# SCH_1_Controller.net
KiCad netlist of a schematic drawn in Altium Designer
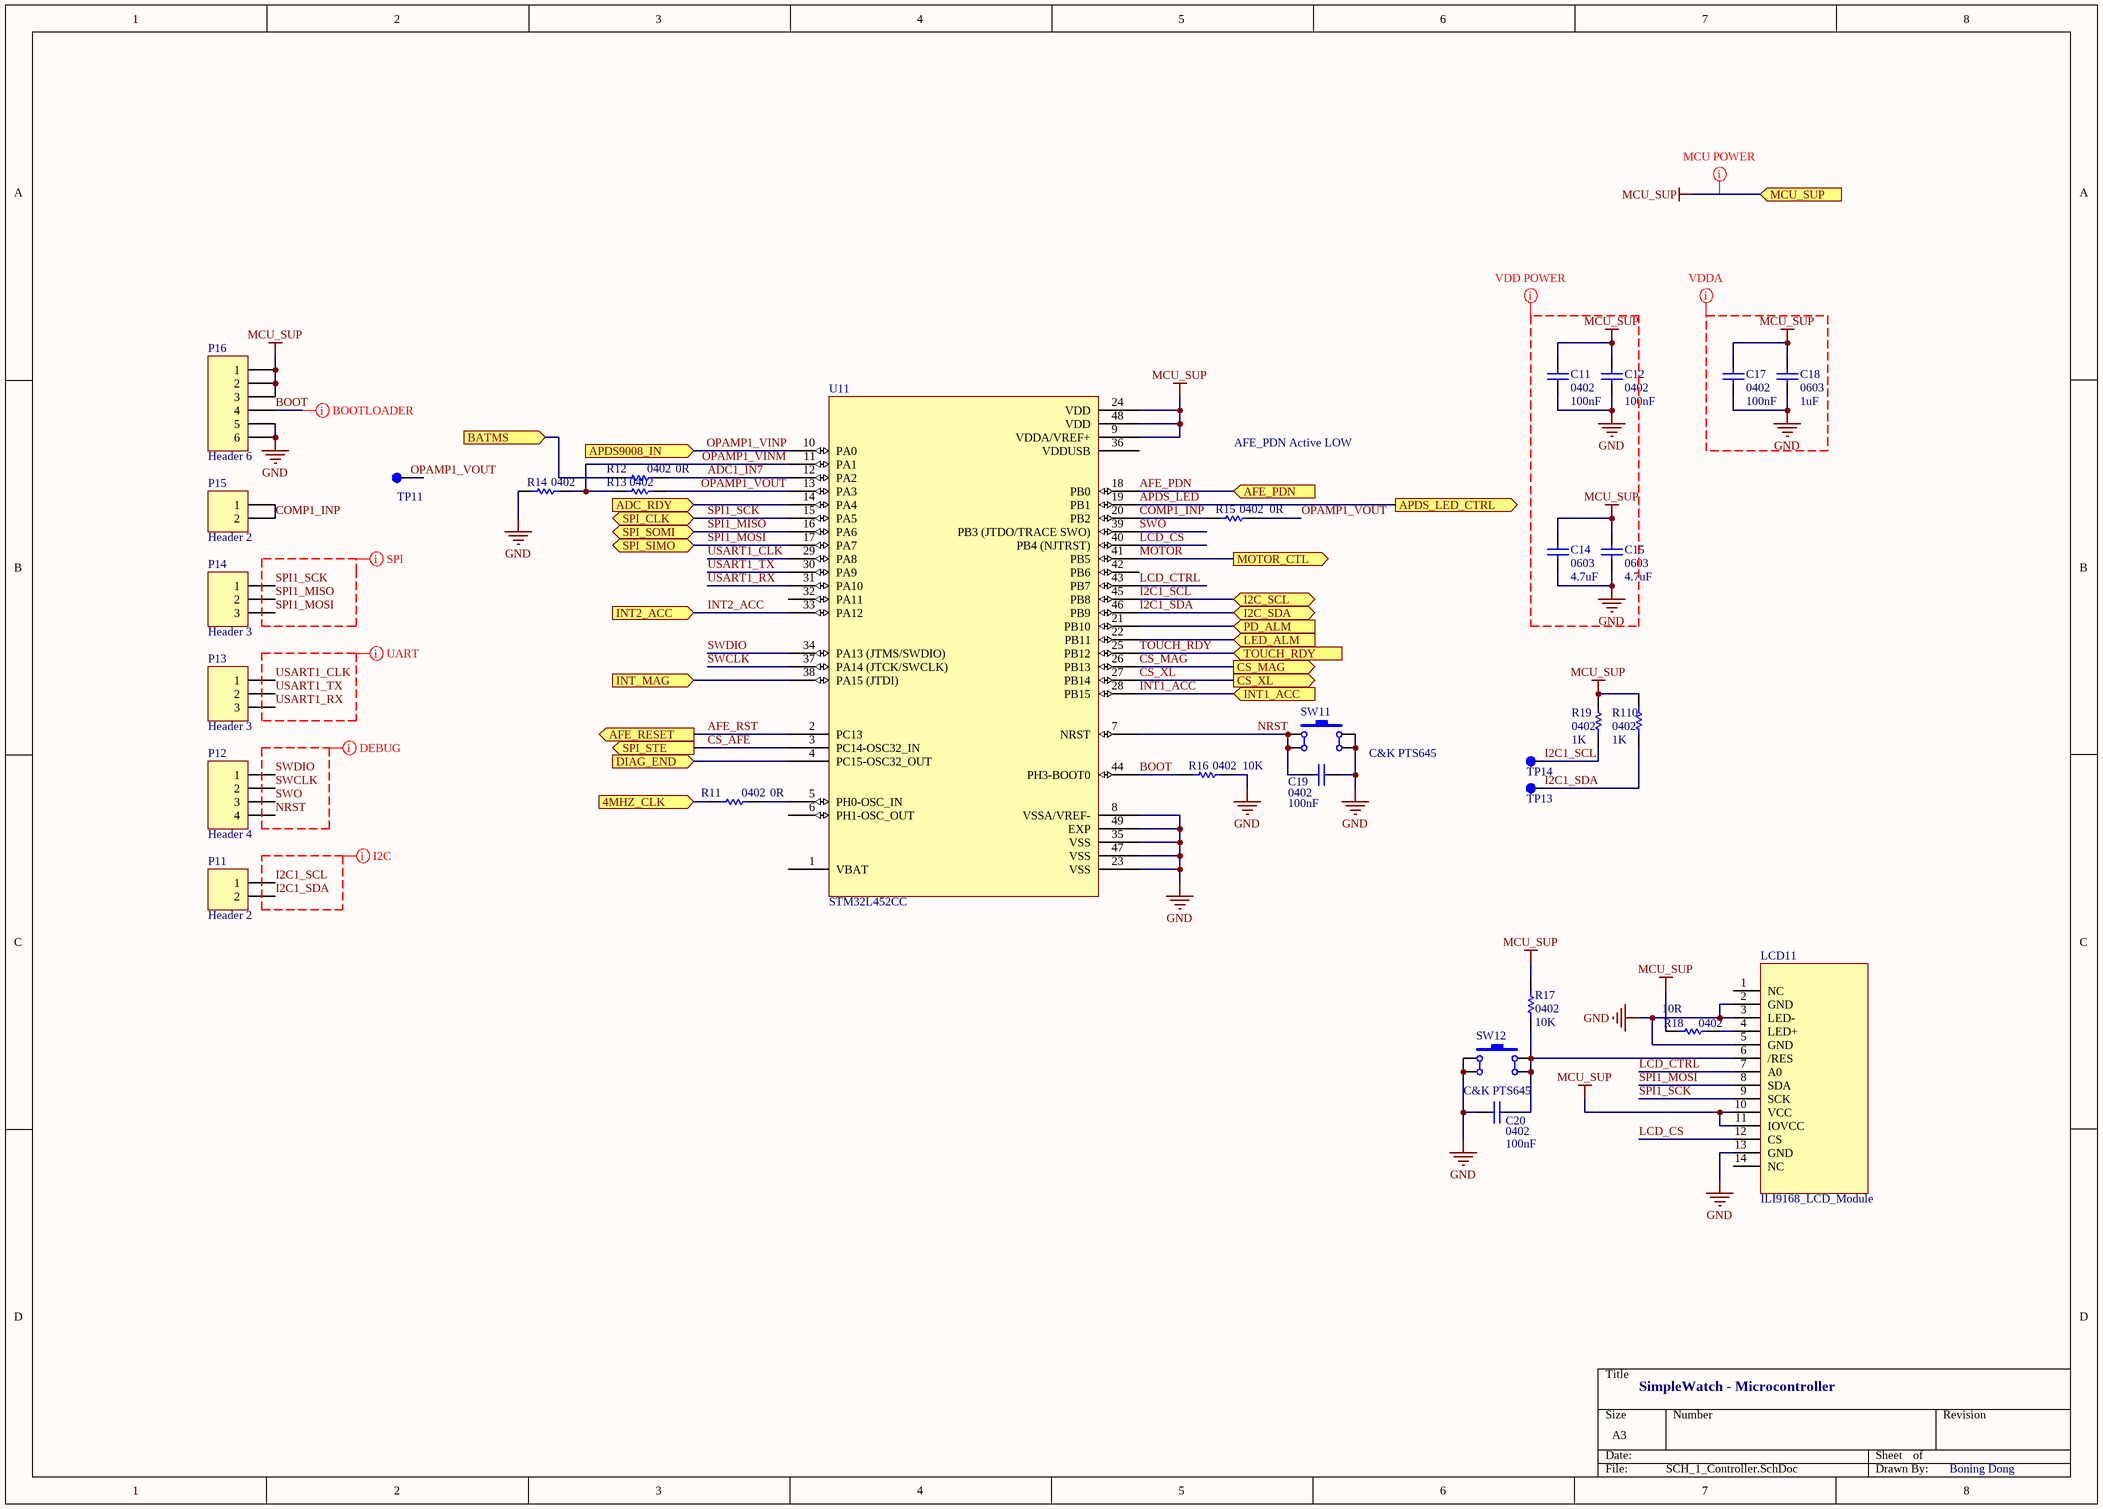
[diagram p0: SCH_1_Controller.SchDoc]

(export (version "E")
  (design (tool "Eeschema 10.0.6"))
  (components
    (comp (ref "C11")
      (value "0402")
      (footprint "CAPC1005X06N")
      (description "Capacitor")
      (fields (field (name "ALTIUM_VALUE") "100nF") (field (name "PUBLISHER") "Altium Limited"))
      (libsource (lib "Miscellaneous Devices") (part "Cap"))
    )
    (comp (ref "C12")
      (value "0402")
      (footprint "CAPC1005X06N")
      (description "Capacitor")
      (fields (field (name "ALTIUM_VALUE") "100nF") (field (name "PUBLISHER") "Altium Limited"))
      (libsource (lib "Miscellaneous Devices") (part "Cap"))
    )
    (comp (ref "C14")
      (value "0603")
      (footprint "CAPC1608X09N")
      (description "Capacitor")
      (fields (field (name "ALTIUM_VALUE") "4.7uF") (field (name "PUBLISHER") "Altium Limited"))
      (libsource (lib "Miscellaneous Devices") (part "Cap"))
    )
    (comp (ref "C15")
      (value "0603")
      (footprint "CAPC1608X09N")
      (description "Capacitor")
      (fields (field (name "ALTIUM_VALUE") "4.7uF") (field (name "PUBLISHER") "Altium Limited"))
      (libsource (lib "Miscellaneous Devices") (part "Cap"))
    )
    (comp (ref "C17")
      (value "0402")
      (footprint "CAPC1005X06N")
      (description "Capacitor")
      (fields (field (name "ALTIUM_VALUE") "100nF") (field (name "PUBLISHER") "Altium Limited"))
      (libsource (lib "Miscellaneous Devices") (part "Cap"))
    )
    (comp (ref "C18")
      (value "0603")
      (footprint "CAPC1608X09N")
      (description "Capacitor")
      (fields (field (name "ALTIUM_VALUE") "1uF") (field (name "PUBLISHER") "Altium Limited"))
      (libsource (lib "Miscellaneous Devices") (part "Cap"))
    )
    (comp (ref "C19")
      (value "0402")
      (footprint "CAPC1005X06N")
      (description "Capacitor")
      (fields (field (name "ALTIUM_VALUE") "100nF") (field (name "PUBLISHER") "Altium Limited"))
      (libsource (lib "Miscellaneous Devices") (part "Cap"))
    )
    (comp (ref "C20")
      (value "0402")
      (footprint "CAPC1005X06N")
      (description "Capacitor")
      (fields (field (name "ALTIUM_VALUE") "100nF") (field (name "PUBLISHER") "Altium Limited"))
      (libsource (lib "Miscellaneous Devices") (part "Cap"))
    )
    (comp (ref "LCD11")
      (value "ILI9168_LCD_Module")
      (footprint "LCD_SMT_128X128")
      (libsource (lib "Schematic_Display") (part "ILI9168_LCD_Module"))
    )
    (comp (ref "P11")
      (value "Header 2")
      (footprint "HDR1X2")
      (description "Header, 2-Pin")
      (fields (field (name "PUBLISHER") "Altium Limited"))
      (libsource (lib "Miscellaneous Connectors") (part "Header 2"))
    )
    (comp (ref "P12")
      (value "Header 4")
      (footprint "HDR1X4")
      (description "Header, 4-Pin")
      (fields (field (name "PUBLISHER") "Altium Limited"))
      (libsource (lib "Miscellaneous Connectors") (part "Header 4"))
    )
    (comp (ref "P13")
      (value "Header 3")
      (footprint "HDR1X3")
      (description "Header, 3-Pin")
      (fields (field (name "PUBLISHER") "Altium Limited"))
      (libsource (lib "Miscellaneous Connectors") (part "Header 3"))
    )
    (comp (ref "P14")
      (value "Header 3")
      (footprint "HDR1X3")
      (description "Header, 3-Pin")
      (fields (field (name "PUBLISHER") "Altium Limited"))
      (libsource (lib "Miscellaneous Connectors") (part "Header 3"))
    )
    (comp (ref "P15")
      (value "Header 2")
      (footprint "HDR1X2")
      (description "Header, 2-Pin")
      (fields (field (name "PUBLISHER") "Altium Limited"))
      (libsource (lib "Miscellaneous Connectors") (part "Header 2"))
    )
    (comp (ref "P16")
      (value "Header 6")
      (footprint "HDR1X6")
      (description "Header, 6-Pin")
      (fields (field (name "PUBLISHER") "Altium Limited"))
      (libsource (lib "Miscellaneous Connectors") (part "Header 6"))
    )
    (comp (ref "R11")
      (value "0402")
      (footprint "RESC1005X04N")
      (description "Resistor")
      (fields (field (name "ALTIUM_VALUE") "0R") (field (name "PUBLISHER") "Altium Limited"))
      (libsource (lib "Miscellaneous Devices") (part "Res1"))
    )
    (comp (ref "R12")
      (value "0402")
      (footprint "RESC1005X04N")
      (description "Resistor")
      (fields (field (name "ALTIUM_VALUE") "0R") (field (name "PUBLISHER") "Altium Limited"))
      (libsource (lib "Miscellaneous Devices") (part "Res1"))
    )
    (comp (ref "R13")
      (value "0402")
      (footprint "RESC1005X04N")
      (description "Resistor")
      (fields (field (name "PUBLISHER") "Altium Limited"))
      (libsource (lib "Miscellaneous Devices") (part "Res1"))
    )
    (comp (ref "R14")
      (value "0402")
      (footprint "RESC1005X04N")
      (description "Resistor")
      (fields (field (name "PUBLISHER") "Altium Limited"))
      (libsource (lib "Miscellaneous Devices") (part "Res1"))
    )
    (comp (ref "R15")
      (value "0402")
      (footprint "RESC1005X04N")
      (description "Resistor")
      (fields (field (name "ALTIUM_VALUE") "0R") (field (name "PUBLISHER") "Altium Limited"))
      (libsource (lib "Miscellaneous Devices") (part "Res1"))
    )
    (comp (ref "R16")
      (value "0402")
      (footprint "RESC1005X04N")
      (description "Resistor")
      (fields (field (name "ALTIUM_VALUE") "10K") (field (name "PUBLISHER") "Altium Limited"))
      (libsource (lib "Miscellaneous Devices") (part "Res1"))
    )
    (comp (ref "R17")
      (value "0402")
      (footprint "RESC1005X04N")
      (description "Resistor")
      (fields (field (name "ALTIUM_VALUE") "10K") (field (name "PUBLISHER") "Altium Limited"))
      (libsource (lib "Miscellaneous Devices") (part "Res1"))
    )
    (comp (ref "R18")
      (value "0402")
      (footprint "RESC1005X04N")
      (description "Resistor")
      (fields (field (name "ALTIUM_VALUE") "10R") (field (name "PUBLISHER") "Altium Limited"))
      (libsource (lib "Miscellaneous Devices") (part "Res1"))
    )
    (comp (ref "R19")
      (value "0402")
      (footprint "RESC1005X04N")
      (description "Resistor")
      (fields (field (name "ALTIUM_VALUE") "1K") (field (name "PUBLISHER") "Altium Limited"))
      (libsource (lib "Miscellaneous Devices") (part "Res1"))
    )
    (comp (ref "R110")
      (value "0402")
      (footprint "RESC1005X04N")
      (description "Resistor")
      (fields (field (name "ALTIUM_VALUE") "1K") (field (name "PUBLISHER") "Altium Limited"))
      (libsource (lib "Miscellaneous Devices") (part "Res1"))
    )
    (comp (ref "SW11")
      (value "C&K PTS645")
      (footprint "C&K_PTS645_SMT")
      (description "General Tactile Switch")
      (libsource (lib "Schematic_Switches") (part "SW_TACT"))
    )
    (comp (ref "SW12")
      (value "C&K PTS645")
      (footprint "C&K_PTS645_SMT")
      (description "General Tactile Switch")
      (libsource (lib "Schematic_Switches") (part "SW_TACT"))
    )
    (comp (ref "TP11")
      (value "TP")
      (footprint "TP100")
      (description "Test Point dot type")
      (libsource (lib "Schematic_Test_Points") (part "TP_A"))
    )
    (comp (ref "TP13")
      (value "TP")
      (footprint "TP100")
      (description "Test Point dot type")
      (libsource (lib "Schematic_Test_Points") (part "TP_A"))
    )
    (comp (ref "TP14")
      (value "TP")
      (footprint "TP100")
      (description "Test Point dot type")
      (libsource (lib "Schematic_Test_Points") (part "TP_A"))
    )
    (comp (ref "U11")
      (value "STM32L452CC")
      (footprint "QFN50P700X700X60-48N_HS550X550")
      (description "ARM® Cortex®-M4 STM32L4 Microcontroller IC 32-Bit 80MHz 512KB (512K x 8) FLASH 48-UFQFPN (7x7)")
      (libsource (lib "Schematic_IC_Micro_Controller") (part "STM32L452CX"))
    )
  )
  (nets
    (net (code "1") (name "/4MHZ_CLK") (class "Default")
      (node (ref "R11") (pin "1") (pinfunction "1_1") (pintype "passive"))
    )
    (net (code "2") (name "/ADC1_IN7") (class "Default")
      (node (ref "R12") (pin "2") (pinfunction "2_2") (pintype "passive"))
      (node (ref "U11") (pin "12") (pinfunction "PA2_12") (pintype "bidirectional"))
    )
    (net (code "3") (name "/ADC_RDY") (class "Default")
      (node (ref "U11") (pin "14") (pinfunction "PA4_14") (pintype "bidirectional"))
    )
    (net (code "4") (name "/AFE_PDN") (class "Default")
      (node (ref "U11") (pin "18") (pinfunction "PB0_18") (pintype "bidirectional"))
    )
    (net (code "5") (name "/AFE_RST") (class "Default")
      (node (ref "U11") (pin "2") (pinfunction "PC13_2") (pintype "passive"))
    )
    (net (code "6") (name "/APDS_LED") (class "Default")
      (node (ref "U11") (pin "19") (pinfunction "PB1_19") (pintype "bidirectional"))
    )
    (net (code "7") (name "/BATMS") (class "Default")
      (node (ref "R12") (pin "1") (pinfunction "1_1") (pintype "passive"))
    )
    (net (code "8") (name "/BOOT") (class "Default")
      (node (ref "P16") (pin "4") (pinfunction "4_4") (pintype "passive"))
      (node (ref "R16") (pin "1") (pinfunction "1_1") (pintype "passive"))
      (node (ref "U11") (pin "44") (pinfunction "PH3-BOOT0_44") (pintype "bidirectional"))
    )
    (net (code "9") (name "/COMP1_INP") (class "Default")
      (node (ref "P15") (pin "1") (pinfunction "1_1") (pintype "passive"))
      (node (ref "P15") (pin "2") (pinfunction "2_2") (pintype "passive"))
      (node (ref "R15") (pin "1") (pinfunction "1_1") (pintype "passive"))
      (node (ref "U11") (pin "20") (pinfunction "PB2_20") (pintype "bidirectional"))
    )
    (net (code "10") (name "/CS_AFE") (class "Default")
      (node (ref "U11") (pin "3") (pinfunction "PC14-OSC32_IN_3") (pintype "passive"))
    )
    (net (code "11") (name "/CS_MAG") (class "Default")
      (node (ref "U11") (pin "26") (pinfunction "PB13_26") (pintype "bidirectional"))
    )
    (net (code "12") (name "/CS_XL") (class "Default")
      (node (ref "U11") (pin "27") (pinfunction "PB14_27") (pintype "bidirectional"))
    )
    (net (code "13") (name "/DIAG_END") (class "Default")
      (node (ref "U11") (pin "4") (pinfunction "PC15-OSC32_OUT_4") (pintype "passive"))
    )
    (net (code "14") (name "/I2C1_SCL") (class "Default")
      (node (ref "P11") (pin "1") (pinfunction "1_1") (pintype "passive"))
      (node (ref "R19") (pin "2") (pinfunction "2_2") (pintype "passive"))
      (node (ref "TP14") (pin "1") (pintype "passive"))
      (node (ref "U11") (pin "45") (pinfunction "PB8_45") (pintype "bidirectional"))
    )
    (net (code "15") (name "/I2C1_SDA") (class "Default")
      (node (ref "P11") (pin "2") (pinfunction "2_2") (pintype "passive"))
      (node (ref "R110") (pin "2") (pinfunction "2_2") (pintype "passive"))
      (node (ref "TP13") (pin "1") (pintype "passive"))
      (node (ref "U11") (pin "46") (pinfunction "PB9_46") (pintype "bidirectional"))
    )
    (net (code "16") (name "/INT1_ACC") (class "Default")
      (node (ref "U11") (pin "28") (pinfunction "PB15_28") (pintype "bidirectional"))
    )
    (net (code "17") (name "/INT2_ACC") (class "Default")
      (node (ref "U11") (pin "33") (pinfunction "PA12_33") (pintype "bidirectional"))
    )
    (net (code "18") (name "/INT_MAG") (class "Default")
      (node (ref "U11") (pin "38") (pinfunction "PA15_(JTDI)_38") (pintype "bidirectional"))
    )
    (net (code "19") (name "/LCD_CS") (class "Default")
      (node (ref "LCD11") (pin "12") (pinfunction "CS_12") (pintype "passive"))
      (node (ref "U11") (pin "40") (pinfunction "PB4_(NJTRST)_40") (pintype "bidirectional"))
    )
    (net (code "20") (name "/LCD_CTRL") (class "Default")
      (node (ref "LCD11") (pin "7") (pinfunction "A0_7") (pintype "passive"))
      (node (ref "U11") (pin "43") (pinfunction "PB7_43") (pintype "bidirectional"))
    )
    (net (code "21") (name "/LED_ALM") (class "Default")
      (node (ref "U11") (pin "22") (pinfunction "PB11_22") (pintype "bidirectional"))
    )
    (net (code "22") (name "/MOTOR") (class "Default")
      (node (ref "U11") (pin "41") (pinfunction "PB5_41") (pintype "bidirectional"))
    )
    (net (code "23") (name "/NRST") (class "Default")
      (node (ref "C19") (pin "2") (pinfunction "2_2") (pintype "passive"))
      (node (ref "P12") (pin "4") (pinfunction "4_4") (pintype "passive"))
      (node (ref "SW11") (pin "1") (pinfunction "1_1") (pintype "passive"))
      (node (ref "SW11") (pin "2") (pinfunction "2_2") (pintype "passive"))
      (node (ref "U11") (pin "7") (pinfunction "NRST_7") (pintype "bidirectional"))
    )
    (net (code "24") (name "/OPAMP1_VINM") (class "Default")
      (node (ref "R13") (pin "1") (pinfunction "1_1") (pintype "passive"))
      (node (ref "R14") (pin "2") (pinfunction "2_2") (pintype "passive"))
      (node (ref "U11") (pin "11") (pinfunction "PA1_11") (pintype "bidirectional"))
    )
    (net (code "25") (name "/OPAMP1_VINP") (class "Default")
      (node (ref "U11") (pin "10") (pinfunction "PA0_10") (pintype "bidirectional"))
    )
    (net (code "26") (name "/OPAMP1_VOUT") (class "Default")
      (node (ref "R13") (pin "2") (pinfunction "2_2") (pintype "passive"))
      (node (ref "R15") (pin "2") (pinfunction "2_2") (pintype "passive"))
      (node (ref "TP11") (pin "1") (pintype "passive"))
      (node (ref "U11") (pin "13") (pinfunction "PA3_13") (pintype "bidirectional"))
    )
    (net (code "27") (name "/PD_ALM") (class "Default")
      (node (ref "U11") (pin "21") (pinfunction "PB10_21") (pintype "bidirectional"))
    )
    (net (code "28") (name "/SPI1_MISO") (class "Default")
      (node (ref "P14") (pin "2") (pinfunction "2_2") (pintype "passive"))
      (node (ref "U11") (pin "16") (pinfunction "PA6_16") (pintype "bidirectional"))
    )
    (net (code "29") (name "/SPI1_MOSI") (class "Default")
      (node (ref "LCD11") (pin "8") (pinfunction "SDA_8") (pintype "passive"))
      (node (ref "P14") (pin "3") (pinfunction "3_3") (pintype "passive"))
      (node (ref "U11") (pin "17") (pinfunction "PA7_17") (pintype "bidirectional"))
    )
    (net (code "30") (name "/SPI1_SCK") (class "Default")
      (node (ref "LCD11") (pin "9") (pinfunction "SCK_9") (pintype "passive"))
      (node (ref "P14") (pin "1") (pinfunction "1_1") (pintype "passive"))
      (node (ref "U11") (pin "15") (pinfunction "PA5_15") (pintype "bidirectional"))
    )
    (net (code "31") (name "/SWCLK") (class "Default")
      (node (ref "P12") (pin "2") (pinfunction "2_2") (pintype "passive"))
      (node (ref "U11") (pin "37") (pinfunction "PA14_(JTCK/SWCLK)_37") (pintype "bidirectional"))
    )
    (net (code "32") (name "/SWDIO") (class "Default")
      (node (ref "P12") (pin "1") (pinfunction "1_1") (pintype "passive"))
      (node (ref "U11") (pin "34") (pinfunction "PA13_(JTMS/SWDIO)_34") (pintype "bidirectional"))
    )
    (net (code "33") (name "/SWO") (class "Default")
      (node (ref "P12") (pin "3") (pinfunction "3_3") (pintype "passive"))
      (node (ref "U11") (pin "39") (pinfunction "PB3_(JTDO/TRACE_SWO)_39") (pintype "bidirectional"))
    )
    (net (code "34") (name "/TOUCH_RDY") (class "Default")
      (node (ref "U11") (pin "25") (pinfunction "PB12_25") (pintype "bidirectional"))
    )
    (net (code "35") (name "/USART1_CLK") (class "Default")
      (node (ref "P13") (pin "1") (pinfunction "1_1") (pintype "passive"))
      (node (ref "U11") (pin "29") (pinfunction "PA8_29") (pintype "bidirectional"))
    )
    (net (code "36") (name "/USART1_RX") (class "Default")
      (node (ref "P13") (pin "3") (pinfunction "3_3") (pintype "passive"))
      (node (ref "U11") (pin "31") (pinfunction "PA10_31") (pintype "bidirectional"))
    )
    (net (code "37") (name "/USART1_TX") (class "Default")
      (node (ref "P13") (pin "2") (pinfunction "2_2") (pintype "passive"))
      (node (ref "U11") (pin "30") (pinfunction "PA9_30") (pintype "bidirectional"))
    )
    (net (code "38") (name "GND") (class "Default")
      (node (ref "C11") (pin "1") (pinfunction "1_1") (pintype "passive"))
      (node (ref "C12") (pin "1") (pinfunction "1_1") (pintype "passive"))
      (node (ref "C14") (pin "1") (pinfunction "1_1") (pintype "passive"))
      (node (ref "C15") (pin "1") (pinfunction "1_1") (pintype "passive"))
      (node (ref "C17") (pin "1") (pinfunction "1_1") (pintype "passive"))
      (node (ref "C18") (pin "1") (pinfunction "1_1") (pintype "passive"))
      (node (ref "C19") (pin "1") (pinfunction "1_1") (pintype "passive"))
      (node (ref "C20") (pin "2") (pinfunction "2_2") (pintype "passive"))
      (node (ref "LCD11") (pin "13") (pinfunction "GND_13") (pintype "passive"))
      (node (ref "LCD11") (pin "2") (pinfunction "GND_2") (pintype "passive"))
      (node (ref "LCD11") (pin "3") (pinfunction "LED-_3") (pintype "passive"))
      (node (ref "LCD11") (pin "5") (pinfunction "GND_5") (pintype "passive"))
      (node (ref "P16") (pin "5") (pinfunction "5_5") (pintype "passive"))
      (node (ref "P16") (pin "6") (pinfunction "6_6") (pintype "passive"))
      (node (ref "R14") (pin "1") (pinfunction "1_1") (pintype "passive"))
      (node (ref "R16") (pin "2") (pinfunction "2_2") (pintype "passive"))
      (node (ref "SW11") (pin "3") (pinfunction "3_3") (pintype "passive"))
      (node (ref "SW11") (pin "4") (pinfunction "4_4") (pintype "passive"))
      (node (ref "SW12") (pin "1") (pinfunction "1_1") (pintype "passive"))
      (node (ref "SW12") (pin "2") (pinfunction "2_2") (pintype "passive"))
      (node (ref "U11") (pin "23") (pinfunction "VSS_23") (pintype "passive"))
      (node (ref "U11") (pin "35") (pinfunction "VSS_35") (pintype "passive"))
      (node (ref "U11") (pin "47") (pinfunction "VSS_47") (pintype "passive"))
      (node (ref "U11") (pin "49") (pinfunction "EXP_49") (pintype "power_in"))
      (node (ref "U11") (pin "8") (pinfunction "VSSA/VREF-_8") (pintype "passive"))
    )
    (net (code "39") (name "MCU_SUP") (class "Default")
      (node (ref "C11") (pin "2") (pinfunction "2_2") (pintype "passive"))
      (node (ref "C12") (pin "2") (pinfunction "2_2") (pintype "passive"))
      (node (ref "C14") (pin "2") (pinfunction "2_2") (pintype "passive"))
      (node (ref "C15") (pin "2") (pinfunction "2_2") (pintype "passive"))
      (node (ref "C17") (pin "2") (pinfunction "2_2") (pintype "passive"))
      (node (ref "C18") (pin "2") (pinfunction "2_2") (pintype "passive"))
      (node (ref "LCD11") (pin "10") (pinfunction "VCC_10") (pintype "passive"))
      (node (ref "LCD11") (pin "11") (pinfunction "IOVCC_11") (pintype "passive"))
      (node (ref "P16") (pin "1") (pinfunction "1_1") (pintype "passive"))
      (node (ref "P16") (pin "2") (pinfunction "2_2") (pintype "passive"))
      (node (ref "P16") (pin "3") (pinfunction "3_3") (pintype "passive"))
      (node (ref "R110") (pin "1") (pinfunction "1_1") (pintype "passive"))
      (node (ref "R17") (pin "2") (pinfunction "2_2") (pintype "passive"))
      (node (ref "R18") (pin "2") (pinfunction "2_2") (pintype "passive"))
      (node (ref "R19") (pin "1") (pinfunction "1_1") (pintype "passive"))
      (node (ref "U11") (pin "24") (pinfunction "VDD_24") (pintype "passive"))
      (node (ref "U11") (pin "48") (pinfunction "VDD_48") (pintype "passive"))
      (node (ref "U11") (pin "9") (pinfunction "VDDA/VREF+_9") (pintype "passive"))
    )
    (net (code "40") (name "Net-(LCD11-LED+)") (class "Default")
      (node (ref "LCD11") (pin "4") (pinfunction "LED+_4") (pintype "passive"))
      (node (ref "R18") (pin "1") (pinfunction "1_1") (pintype "passive"))
    )
    (net (code "41") (name "Net-(LCD11-{slash}RES)") (class "Default")
      (node (ref "C20") (pin "1") (pinfunction "1_1") (pintype "passive"))
      (node (ref "LCD11") (pin "6") (pinfunction "/RES_6") (pintype "passive"))
      (node (ref "R17") (pin "1") (pinfunction "1_1") (pintype "passive"))
      (node (ref "SW12") (pin "3") (pinfunction "3_3") (pintype "passive"))
      (node (ref "SW12") (pin "4") (pinfunction "4_4") (pintype "passive"))
    )
    (net (code "42") (name "Net-(U11-PH0-OSC_IN)") (class "Default")
      (node (ref "R11") (pin "2") (pinfunction "2_2") (pintype "passive"))
      (node (ref "U11") (pin "5") (pinfunction "PH0-OSC_IN_5") (pintype "bidirectional"))
    )
    (net (code "43") (name "unconnected-(LCD11-NC-Pad1)") (class "Default")
      (node (ref "LCD11") (pin "1") (pinfunction "NC_1") (pintype "passive"))
    )
    (net (code "44") (name "unconnected-(LCD11-NC-Pad14)") (class "Default")
      (node (ref "LCD11") (pin "14") (pinfunction "NC_14") (pintype "passive"))
    )
    (net (code "45") (name "unconnected-(U11-PA11-Pad32)") (class "Default")
      (node (ref "U11") (pin "32") (pinfunction "PA11_32") (pintype "bidirectional"))
    )
    (net (code "46") (name "unconnected-(U11-PB6-Pad42)") (class "Default")
      (node (ref "U11") (pin "42") (pinfunction "PB6_42") (pintype "bidirectional"))
    )
    (net (code "47") (name "unconnected-(U11-PH1-OSC_OUT-Pad6)") (class "Default")
      (node (ref "U11") (pin "6") (pinfunction "PH1-OSC_OUT_6") (pintype "bidirectional"))
    )
    (net (code "48") (name "unconnected-(U11-VBAT-Pad1)") (class "Default")
      (node (ref "U11") (pin "1") (pinfunction "VBAT_1") (pintype "passive"))
    )
    (net (code "49") (name "unconnected-(U11-VDDUSB-Pad36)") (class "Default")
      (node (ref "U11") (pin "36") (pinfunction "VDDUSB_36") (pintype "passive"))
    )
  )
)
